# LED-TEST-Eagle.net
KiCad netlist of a schematic drawn in EAGLE
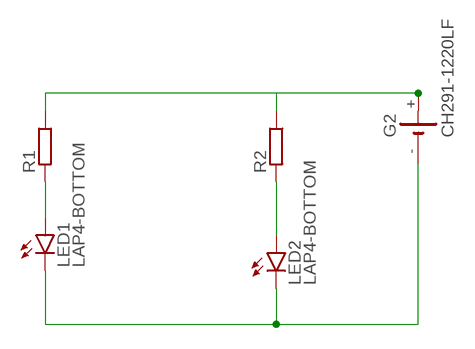
[diagram p0: schematic, sheet 1]

(export (version "E")
  (design (tool "Eeschema 10.0.6"))
  (components
    (comp (ref "G2")
      (value "CH291-1220LF")
      (footprint "eagle-import:CH291-1220LF")
      (libsource (lib "eagle-import") (part "CH291-1220LF"))
    )
    (comp (ref "LED1")
      (value "LAP4-BOTTOM")
      (footprint "eagle-import:P47F-BOTTOM")
      (libsource (lib "eagle-import") (part "P4-BOTTOMLA"))
    )
    (comp (ref "LED2")
      (value "LAP4-BOTTOM")
      (footprint "eagle-import:P47F-BOTTOM")
      (libsource (lib "eagle-import") (part "P4-BOTTOMLA"))
    )
    (comp (ref "R1")
      (value "SMT-WAV")
      (footprint "eagle-import:SMT-WAV")
      (libsource (lib "eagle-import") (part "SMT-WAV"))
    )
    (comp (ref "R2")
      (value "SMT-WAV")
      (footprint "eagle-import:SMT-WAV")
      (libsource (lib "eagle-import") (part "SMT-WAV"))
    )
  )
  (nets
    (net (code "1") (name "Net-(G2-Pad+)") (class "Default")
      (node (ref "G2") (pin "+") (pinfunction "+_+") (pintype "passive"))
      (node (ref "R1") (pin "1") (pinfunction "1_1") (pintype "passive"))
      (node (ref "R2") (pin "1") (pinfunction "1_1") (pintype "passive"))
    )
    (net (code "2") (name "Net-(G2-Pad-)") (class "Default")
      (node (ref "G2") (pin "-") (pinfunction "-_-") (pintype "passive"))
      (node (ref "LED1") (pin "C") (pinfunction "C_C") (pintype "passive"))
      (node (ref "LED2") (pin "C") (pinfunction "C_C") (pintype "passive"))
    )
    (net (code "3") (name "Net-(LED1-PadA)") (class "Default")
      (node (ref "LED1") (pin "A") (pinfunction "A_A") (pintype "passive"))
      (node (ref "R1") (pin "2") (pinfunction "2_2") (pintype "passive"))
    )
    (net (code "4") (name "Net-(LED2-PadA)") (class "Default")
      (node (ref "LED2") (pin "A") (pinfunction "A_A") (pintype "passive"))
      (node (ref "R2") (pin "2") (pinfunction "2_2") (pintype "passive"))
    )
  )
)
